# Sensor.net
KiCad netlist of a schematic drawn in Altium Designer
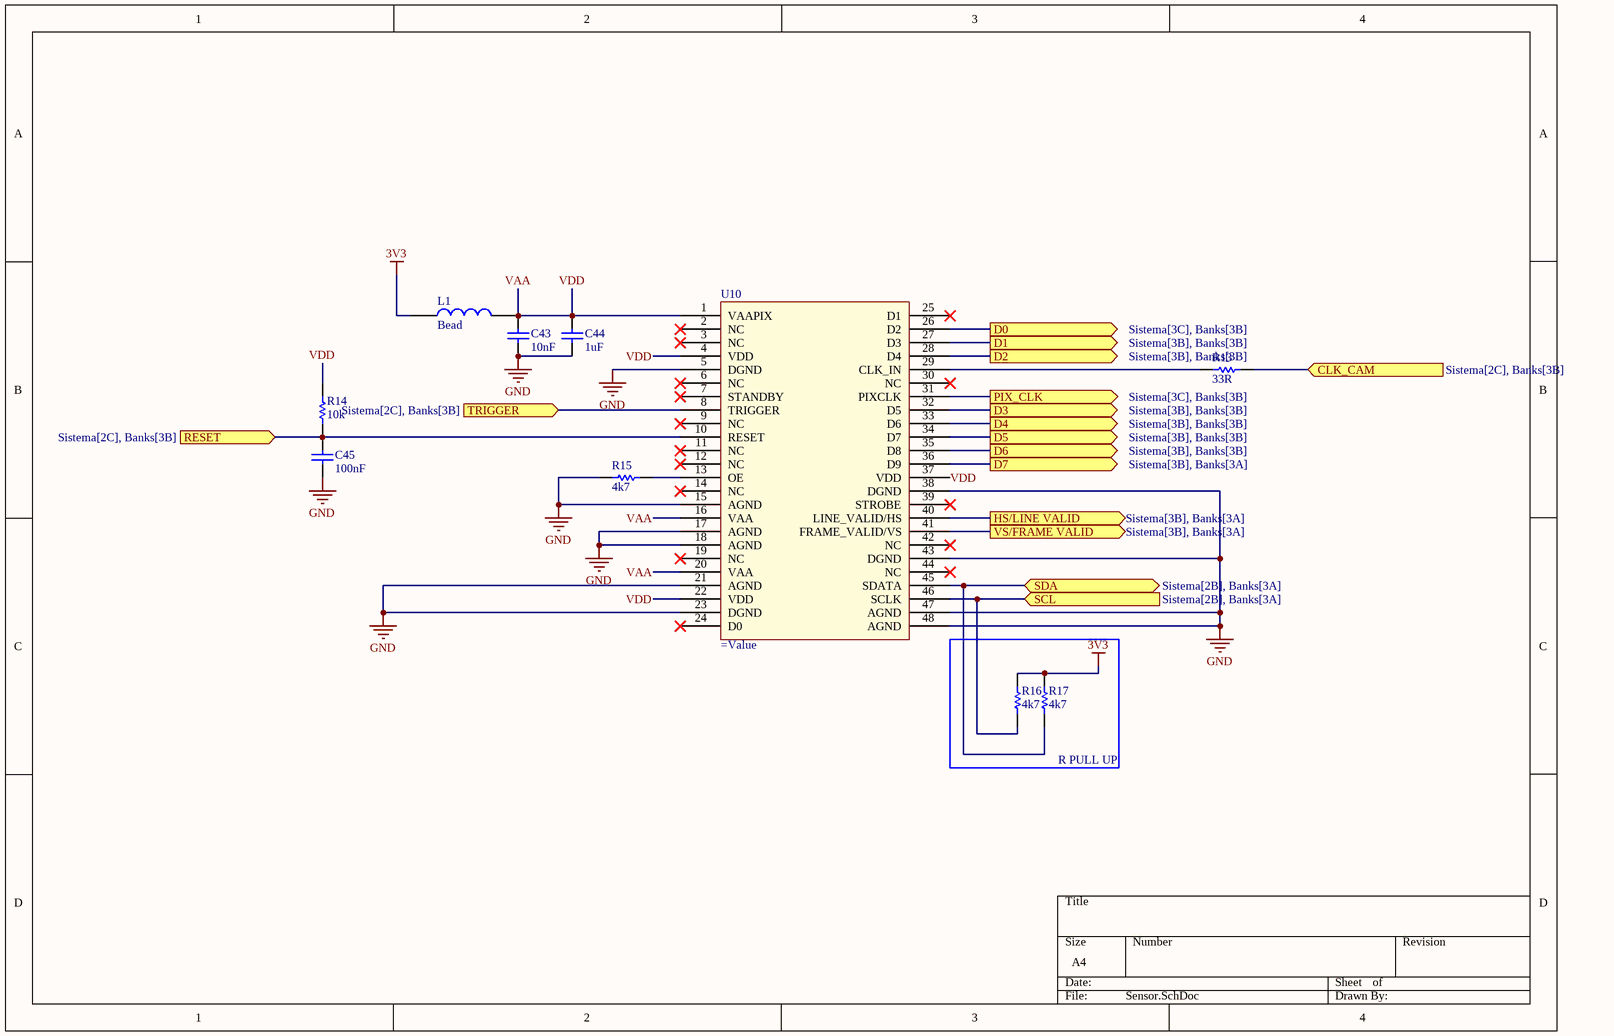
[diagram p0: Sensor.SchDoc]

(export (version "E")
  (design (tool "Eeschema 10.0.6"))
  (components
    (comp (ref "C43")
      (value "10nF")
      (footprint "C_0805_2013_b")
      (description "Capacitor SMD 0805")
      (fields (field (name "TOLERANCE") "5%") (field (name "MANUFACTURER") "KEMET"))
      (libsource (lib "MyLibraryV2") (part "C_10nF_50V_b"))
    )
    (comp (ref "C44")
      (value "1uF")
      (footprint "C_0805_2013_b")
      (description "Capacitor SMD 0805")
      (fields
        (field (name "MANUFACTURER") "Cal-Chip Electronics")
        (field (name "MANUFACTURER PART NUMBER") "GMC21X7R105K50NT")
      )
      (libsource (lib "MyLibraryV2") (part "C_1uF_50V_b"))
    )
    (comp (ref "C45")
      (value "100nF")
      (footprint "C_0805_2013_b")
      (description "Capacitor SMD 0805")
      (fields (field (name "TOLERANCE") "10%") (field (name "VOLTAGE") "50V"))
      (libsource (lib "MyLibraryV2") (part "C_100nF_50V_b"))
    )
    (comp (ref "L1")
      (value "Bead")
      (footprint "L_0805_2013")
      (description "Inductor SMD 0805")
      (fields
        (field (name "MANUFACTURER") "Pulse")
        (field (name "MANUFACTURER PART NUMBER") "PE-0805PFB600ST")
      )
      (libsource (lib "MyLibraryV2") (part "L_Bead"))
    )
    (comp (ref "R13")
      (value "33R")
      (footprint "R_0805_2012_a")
      (description "Resistor SMD 0805")
      (fields (field (name "TOLERANCE") "1%") (field (name "MANUFACTURER") "Stackpole Electronics"))
      (libsource (lib "MyLibraryV2") (part "R_33R_b"))
    )
    (comp (ref "R14")
      (value "10k")
      (footprint "R_0805_2012_a")
      (description "Resistor SMD 0805")
      (fields (field (name "TOLERANCE") "1%") (field (name "MANUFACTURER") "Yageo"))
      (libsource (lib "MyLibraryV2") (part "R_10k_b"))
    )
    (comp (ref "R15")
      (value "4k7")
      (footprint "R_0805_2012_a")
      (description "Resistor SMD 0805")
      (fields (field (name "TOLERANCE") "1%") (field (name "MANUFACTURER") "Stackpole Electronics"))
      (libsource (lib "MyLibraryV2") (part "R_4k7_b"))
    )
    (comp (ref "R16")
      (value "4k7")
      (footprint "R_0805_2012_a")
      (description "Resistor SMD 0805")
      (fields (field (name "TOLERANCE") "1%") (field (name "MANUFACTURER") "Stackpole Electronics"))
      (libsource (lib "MyLibraryV2") (part "R_4k7_b"))
    )
    (comp (ref "R17")
      (value "4k7")
      (footprint "R_0805_2012_a")
      (description "Resistor SMD 0805")
      (fields (field (name "TOLERANCE") "1%") (field (name "MANUFACTURER") "Stackpole Electronics"))
      (libsource (lib "MyLibraryV2") (part "R_4k7_b"))
    )
    (comp (ref "U10")
      (value "~")
      (footprint "U_CLCC48_SOCKET")
      (description "SENSOR 1/2 PULGADA 1 MEGAPIXEL")
      (libsource (lib "Mi_lib") (part "MT9M001C12STM"))
    )
  )
  (nets
    (net (code "1") (name "/CLK_CAM") (class "Default")
      (node (ref "R13") (pin "2") (pinfunction "2_2") (pintype "passive"))
    )
    (net (code "2") (name "/D0") (class "Default")
      (node (ref "U10") (pin "26") (pinfunction "D2_26") (pintype "passive"))
    )
    (net (code "3") (name "/D1") (class "Default")
      (node (ref "U10") (pin "27") (pinfunction "D3_27") (pintype "passive"))
    )
    (net (code "4") (name "/D2") (class "Default")
      (node (ref "U10") (pin "28") (pinfunction "D4_28") (pintype "passive"))
    )
    (net (code "5") (name "/D3") (class "Default")
      (node (ref "U10") (pin "32") (pinfunction "D5_32") (pintype "passive"))
    )
    (net (code "6") (name "/D4") (class "Default")
      (node (ref "U10") (pin "33") (pinfunction "D6_33") (pintype "passive"))
    )
    (net (code "7") (name "/D5") (class "Default")
      (node (ref "U10") (pin "34") (pinfunction "D7_34") (pintype "passive"))
    )
    (net (code "8") (name "/D6") (class "Default")
      (node (ref "U10") (pin "35") (pinfunction "D8_35") (pintype "passive"))
    )
    (net (code "9") (name "/D7") (class "Default")
      (node (ref "U10") (pin "36") (pinfunction "D9_36") (pintype "passive"))
    )
    (net (code "10") (name "/HS{slash}LINE VALID") (class "Default")
      (node (ref "U10") (pin "40") (pinfunction "LINE_VALID/HS_40") (pintype "passive"))
    )
    (net (code "11") (name "/PIX_CLK") (class "Default")
      (node (ref "U10") (pin "31") (pinfunction "PIXCLK_31") (pintype "passive"))
    )
    (net (code "12") (name "/RESET") (class "Default")
      (node (ref "C45") (pin "2") (pinfunction "2_2") (pintype "passive"))
      (node (ref "R14") (pin "1") (pinfunction "1_1") (pintype "passive"))
      (node (ref "U10") (pin "10") (pinfunction "RESET_10") (pintype "passive"))
    )
    (net (code "13") (name "/SCL") (class "Default")
      (node (ref "R16") (pin "1") (pinfunction "1_1") (pintype "passive"))
      (node (ref "U10") (pin "46") (pinfunction "SCLK_46") (pintype "passive"))
    )
    (net (code "14") (name "/SDA") (class "Default")
      (node (ref "R17") (pin "1") (pinfunction "1_1") (pintype "passive"))
      (node (ref "U10") (pin "45") (pinfunction "SDATA_45") (pintype "passive"))
    )
    (net (code "15") (name "/TRIGGER") (class "Default")
      (node (ref "U10") (pin "8") (pinfunction "TRIGGER_8") (pintype "passive"))
    )
    (net (code "16") (name "/VAA") (class "Default")
      (node (ref "C43") (pin "2") (pinfunction "2_2") (pintype "passive"))
      (node (ref "C44") (pin "2") (pinfunction "2_2") (pintype "passive"))
      (node (ref "L1") (pin "2") (pinfunction "2_2") (pintype "passive"))
      (node (ref "R14") (pin "2") (pinfunction "2_2") (pintype "passive"))
      (node (ref "U10") (pin "1") (pinfunction "VAAPIX_1") (pintype "passive"))
      (node (ref "U10") (pin "16") (pinfunction "VAA_16") (pintype "passive"))
      (node (ref "U10") (pin "20") (pinfunction "VAA_20") (pintype "passive"))
      (node (ref "U10") (pin "22") (pinfunction "VDD_22") (pintype "passive"))
      (node (ref "U10") (pin "37") (pinfunction "VDD_37") (pintype "passive"))
      (node (ref "U10") (pin "4") (pinfunction "VDD_4") (pintype "passive"))
    )
    (net (code "17") (name "/VS{slash}FRAME VALID") (class "Default")
      (node (ref "U10") (pin "41") (pinfunction "FRAME_VALID/VS_41") (pintype "passive"))
    )
    (net (code "18") (name "3V3") (class "Default")
      (node (ref "L1") (pin "1") (pinfunction "1_1") (pintype "passive"))
      (node (ref "R16") (pin "2") (pinfunction "2_2") (pintype "passive"))
      (node (ref "R17") (pin "2") (pinfunction "2_2") (pintype "passive"))
    )
    (net (code "19") (name "GND") (class "Default")
      (node (ref "C43") (pin "1") (pinfunction "1_1") (pintype "passive"))
      (node (ref "C44") (pin "1") (pinfunction "1_1") (pintype "passive"))
      (node (ref "C45") (pin "1") (pinfunction "1_1") (pintype "passive"))
      (node (ref "R15") (pin "1") (pinfunction "1_1") (pintype "passive"))
      (node (ref "U10") (pin "15") (pinfunction "AGND_15") (pintype "passive"))
      (node (ref "U10") (pin "17") (pinfunction "AGND_17") (pintype "passive"))
      (node (ref "U10") (pin "18") (pinfunction "AGND_18") (pintype "passive"))
      (node (ref "U10") (pin "21") (pinfunction "AGND_21") (pintype "passive"))
      (node (ref "U10") (pin "23") (pinfunction "DGND_23") (pintype "passive"))
      (node (ref "U10") (pin "38") (pinfunction "DGND_38") (pintype "passive"))
      (node (ref "U10") (pin "43") (pinfunction "DGND_43") (pintype "passive"))
      (node (ref "U10") (pin "47") (pinfunction "AGND_47") (pintype "passive"))
      (node (ref "U10") (pin "48") (pinfunction "AGND_48") (pintype "passive"))
      (node (ref "U10") (pin "5") (pinfunction "DGND_5") (pintype "passive"))
    )
    (net (code "20") (name "Net-(U10-CLK_IN)") (class "Default")
      (node (ref "R13") (pin "1") (pinfunction "1_1") (pintype "passive"))
      (node (ref "U10") (pin "29") (pinfunction "CLK_IN_29") (pintype "passive"))
    )
    (net (code "21") (name "Net-(U10-OE)") (class "Default")
      (node (ref "R15") (pin "2") (pinfunction "2_2") (pintype "passive"))
      (node (ref "U10") (pin "13") (pinfunction "OE_13") (pintype "passive"))
    )
    (net (code "22") (name "unconnected-(U10-D0-Pad24)") (class "Default")
      (node (ref "U10") (pin "24") (pinfunction "D0_24") (pintype "passive+no_connect"))
    )
    (net (code "23") (name "unconnected-(U10-D1-Pad25)") (class "Default")
      (node (ref "U10") (pin "25") (pinfunction "D1_25") (pintype "passive+no_connect"))
    )
    (net (code "24") (name "unconnected-(U10-NC-Pad2)") (class "Default")
      (node (ref "U10") (pin "2") (pinfunction "NC_2") (pintype "passive+no_connect"))
    )
    (net (code "25") (name "unconnected-(U10-NC-Pad3)") (class "Default")
      (node (ref "U10") (pin "3") (pinfunction "NC_3") (pintype "passive+no_connect"))
    )
    (net (code "26") (name "unconnected-(U10-NC-Pad6)") (class "Default")
      (node (ref "U10") (pin "6") (pinfunction "NC_6") (pintype "passive+no_connect"))
    )
    (net (code "27") (name "unconnected-(U10-NC-Pad9)") (class "Default")
      (node (ref "U10") (pin "9") (pinfunction "NC_9") (pintype "passive+no_connect"))
    )
    (net (code "28") (name "unconnected-(U10-NC-Pad11)") (class "Default")
      (node (ref "U10") (pin "11") (pinfunction "NC_11") (pintype "passive+no_connect"))
    )
    (net (code "29") (name "unconnected-(U10-NC-Pad12)") (class "Default")
      (node (ref "U10") (pin "12") (pinfunction "NC_12") (pintype "passive+no_connect"))
    )
    (net (code "30") (name "unconnected-(U10-NC-Pad14)") (class "Default")
      (node (ref "U10") (pin "14") (pinfunction "NC_14") (pintype "passive+no_connect"))
    )
    (net (code "31") (name "unconnected-(U10-NC-Pad19)") (class "Default")
      (node (ref "U10") (pin "19") (pinfunction "NC_19") (pintype "passive+no_connect"))
    )
    (net (code "32") (name "unconnected-(U10-NC-Pad30)") (class "Default")
      (node (ref "U10") (pin "30") (pinfunction "NC_30") (pintype "passive+no_connect"))
    )
    (net (code "33") (name "unconnected-(U10-NC-Pad42)") (class "Default")
      (node (ref "U10") (pin "42") (pinfunction "NC_42") (pintype "passive+no_connect"))
    )
    (net (code "34") (name "unconnected-(U10-NC-Pad44)") (class "Default")
      (node (ref "U10") (pin "44") (pinfunction "NC_44") (pintype "passive+no_connect"))
    )
    (net (code "35") (name "unconnected-(U10-STANDBY-Pad7)") (class "Default")
      (node (ref "U10") (pin "7") (pinfunction "STANDBY_7") (pintype "passive+no_connect"))
    )
    (net (code "36") (name "unconnected-(U10-STROBE-Pad39)") (class "Default")
      (node (ref "U10") (pin "39") (pinfunction "STROBE_39") (pintype "passive+no_connect"))
    )
  )
)
